# 3V3BUCK.net
KiCad netlist of a schematic drawn in Altium Designer
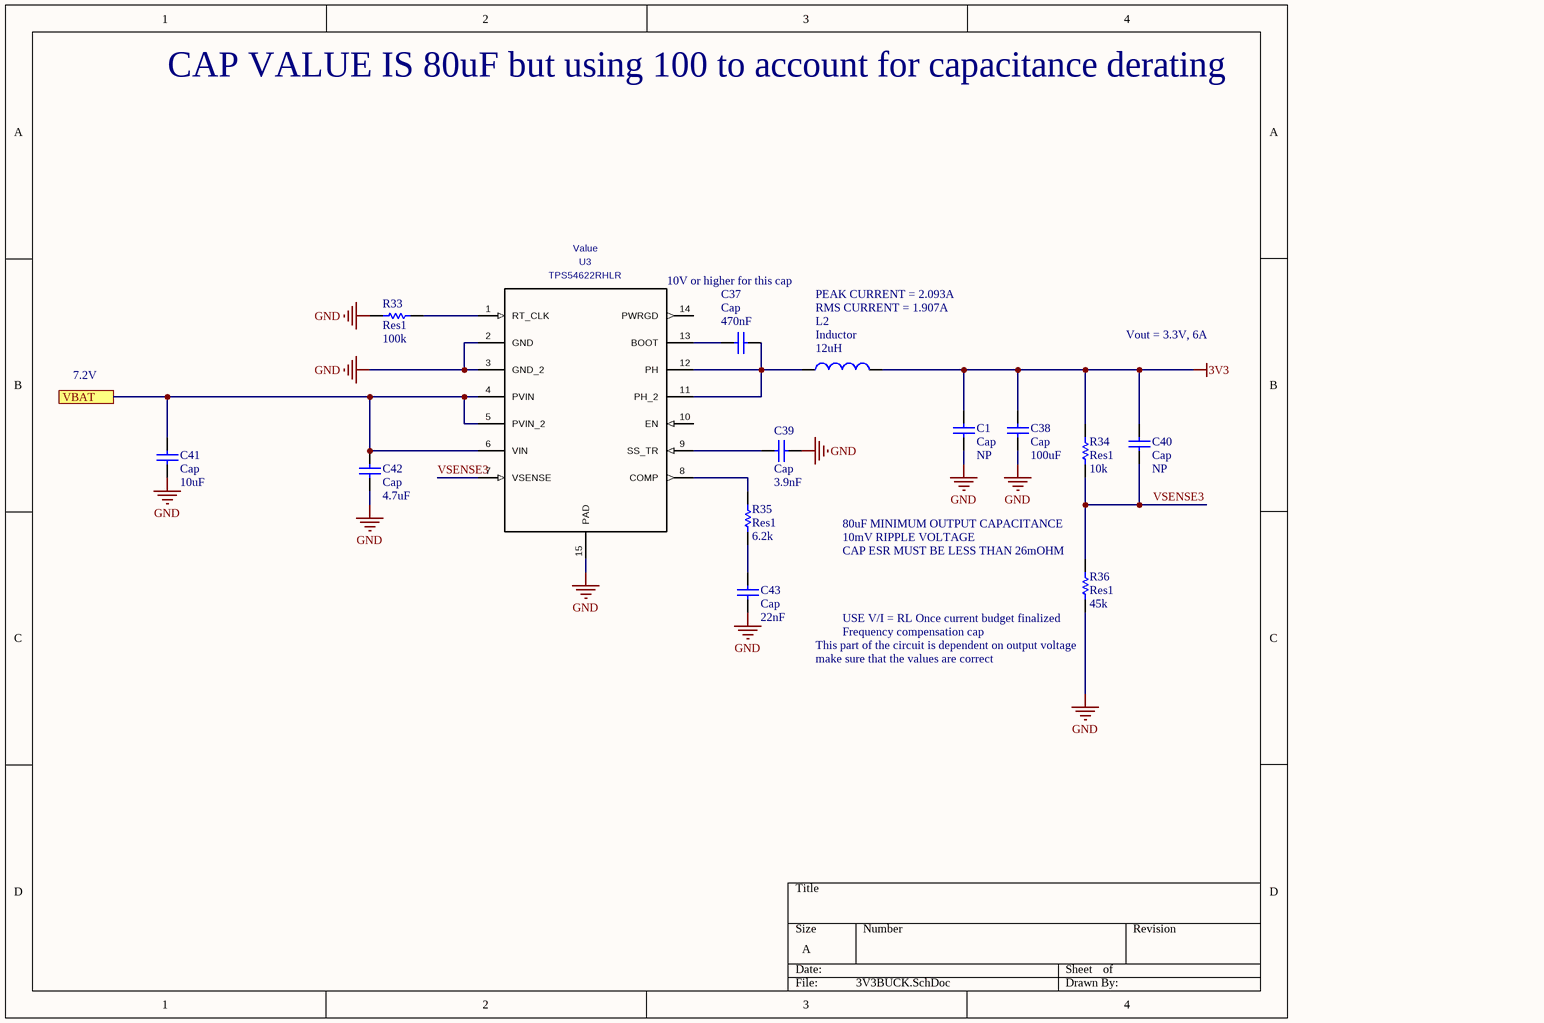
[diagram p0: 3V3BUCK.SchDoc]

(export (version "E")
  (design (tool "Eeschema 10.0.6"))
  (components
    (comp (ref "C1")
      (value "Cap")
      (footprint "1608[0603]")
      (description "Capacitor")
      (fields (field (name "ALTIUM_VALUE") "NP") (field (name "PUBLISHER") "Altium Limited"))
      (libsource (lib "Miscellaneous Devices") (part "Cap"))
    )
    (comp (ref "C37")
      (value "Cap")
      (footprint "0402-A")
      (description "Capacitor")
      (fields (field (name "ALTIUM_VALUE") "470nF") (field (name "PUBLISHER") "Altium Limited"))
      (libsource (lib "Miscellaneous Devices") (part "Cap"))
    )
    (comp (ref "C38")
      (value "Cap")
      (footprint "C1210")
      (description "Capacitor")
      (fields (field (name "ALTIUM_VALUE") "100uF") (field (name "PUBLISHER") "Altium Limited"))
      (libsource (lib "Miscellaneous Devices") (part "Cap"))
    )
    (comp (ref "C39")
      (value "Cap")
      (footprint "0402-A")
      (description "Capacitor")
      (fields (field (name "ALTIUM_VALUE") "3.9nF") (field (name "PUBLISHER") "Altium Limited"))
      (libsource (lib "Miscellaneous Devices") (part "Cap"))
    )
    (comp (ref "C40")
      (value "Cap")
      (footprint "1608[0603]")
      (description "Capacitor")
      (fields (field (name "ALTIUM_VALUE") "NP") (field (name "PUBLISHER") "Altium Limited"))
      (libsource (lib "Miscellaneous Devices") (part "Cap"))
    )
    (comp (ref "C41")
      (value "Cap")
      (footprint "6-0805_M")
      (description "Capacitor")
      (fields (field (name "ALTIUM_VALUE") "10uF") (field (name "PUBLISHER") "Altium Limited"))
      (libsource (lib "Miscellaneous Devices") (part "Cap"))
    )
    (comp (ref "C42")
      (value "Cap")
      (footprint "6-0805_M")
      (description "Capacitor")
      (fields (field (name "ALTIUM_VALUE") "4.7uF") (field (name "PUBLISHER") "Altium Limited"))
      (libsource (lib "Miscellaneous Devices") (part "Cap"))
    )
    (comp (ref "C43")
      (value "Cap")
      (footprint "0402-A")
      (description "Capacitor")
      (fields (field (name "ALTIUM_VALUE") "22nF") (field (name "PUBLISHER") "Altium Limited"))
      (libsource (lib "Miscellaneous Devices") (part "Cap"))
    )
    (comp (ref "L2")
      (value "Inductor")
      (footprint "IND_BOURNS_SRR1260")
      (fields (field (name "ALTIUM_VALUE") "12uH") (field (name "PUBLISHER") "Altium Limited"))
      (libsource (lib "Miscellaneous Devices") (part "Inductor"))
    )
    (comp (ref "R33")
      (value "Res1")
      (footprint "0402-A")
      (description "Resistor")
      (fields (field (name "ALTIUM_VALUE") "100k") (field (name "PUBLISHER") "Altium Limited"))
      (libsource (lib "Miscellaneous Devices") (part "Res1"))
    )
    (comp (ref "R34")
      (value "Res1")
      (footprint "0402-A")
      (description "Resistor")
      (fields (field (name "ALTIUM_VALUE") "10k") (field (name "PUBLISHER") "Altium Limited"))
      (libsource (lib "Miscellaneous Devices") (part "Res1"))
    )
    (comp (ref "R35")
      (value "Res1")
      (footprint "0402-A")
      (description "Resistor")
      (fields (field (name "ALTIUM_VALUE") "6.2k") (field (name "PUBLISHER") "Altium Limited"))
      (libsource (lib "Miscellaneous Devices") (part "Res1"))
    )
    (comp (ref "R36")
      (value "Res1")
      (footprint "0402-A")
      (description "Resistor 1%")
      (fields (field (name "ALTIUM_VALUE") "45k") (field (name "PUBLISHER") "Altium Limited"))
      (libsource (lib "Miscellaneous Devices") (part "Res1"))
    )
    (comp (ref "U3")
      (value "TPS54622RHLR")
      (footprint "RHL0014A")
      (fields (field (name "MANUFACTURER") "Texas Instruments") (field (name "ALTIUM_VALUE") "Value"))
      (libsource (lib "AltiumV15") (part "TPS54622RHLR"))
    )
  )
  (nets
    (net (code "1") (name "/VBAT") (class "Default")
      (node (ref "C41") (pin "2") (pinfunction "2_2") (pintype "passive"))
      (node (ref "C42") (pin "2") (pinfunction "2_2") (pintype "passive"))
      (node (ref "U3") (pin "4") (pinfunction "PVIN_4") (pintype "power_in"))
      (node (ref "U3") (pin "5") (pinfunction "PVIN_2_5") (pintype "power_in"))
      (node (ref "U3") (pin "6") (pinfunction "VIN_6") (pintype "power_in"))
    )
    (net (code "2") (name "/VSENSE3") (class "Default")
      (node (ref "C40") (pin "1") (pinfunction "1_1") (pintype "passive"))
      (node (ref "R34") (pin "2") (pinfunction "2_2") (pintype "passive"))
      (node (ref "R36") (pin "2") (pinfunction "2_2") (pintype "passive"))
      (node (ref "U3") (pin "7") (pinfunction "VSENSE_7") (pintype "input"))
    )
    (net (code "3") (name "3V3") (class "Default")
      (node (ref "C1") (pin "2") (pinfunction "2_2") (pintype "passive"))
      (node (ref "C38") (pin "2") (pinfunction "2_2") (pintype "passive"))
      (node (ref "C40") (pin "2") (pinfunction "2_2") (pintype "passive"))
      (node (ref "L2") (pin "2") (pinfunction "2_2") (pintype "passive"))
      (node (ref "R34") (pin "1") (pinfunction "1_1") (pintype "passive"))
    )
    (net (code "4") (name "GND") (class "Default")
      (node (ref "C1") (pin "1") (pinfunction "1_1") (pintype "passive"))
      (node (ref "C38") (pin "1") (pinfunction "1_1") (pintype "passive"))
      (node (ref "C39") (pin "1") (pinfunction "1_1") (pintype "passive"))
      (node (ref "C41") (pin "1") (pinfunction "1_1") (pintype "passive"))
      (node (ref "C42") (pin "1") (pinfunction "1_1") (pintype "passive"))
      (node (ref "C43") (pin "1") (pinfunction "1_1") (pintype "passive"))
      (node (ref "R33") (pin "1") (pinfunction "1_1") (pintype "passive"))
      (node (ref "R36") (pin "1") (pinfunction "1_1") (pintype "passive"))
      (node (ref "U3") (pin "15") (pinfunction "PAD_15") (pintype "power_in"))
      (node (ref "U3") (pin "2") (pinfunction "GND_2") (pintype "power_in"))
      (node (ref "U3") (pin "3") (pinfunction "GND_2_3") (pintype "power_in"))
    )
    (net (code "5") (name "Net-(C43-Pad2)") (class "Default")
      (node (ref "C43") (pin "2") (pinfunction "2_2") (pintype "passive"))
      (node (ref "R35") (pin "1") (pinfunction "1_1") (pintype "passive"))
    )
    (net (code "6") (name "Net-(U3-BOOT)") (class "Default")
      (node (ref "C37") (pin "1") (pinfunction "1_1") (pintype "passive"))
      (node (ref "U3") (pin "13") (pinfunction "BOOT_13") (pintype "power_in"))
    )
    (net (code "7") (name "Net-(U3-COMP)") (class "Default")
      (node (ref "R35") (pin "2") (pinfunction "2_2") (pintype "passive"))
      (node (ref "U3") (pin "8") (pinfunction "COMP_8") (pintype "output"))
    )
    (net (code "8") (name "Net-(U3-PH)") (class "Default")
      (node (ref "C37") (pin "2") (pinfunction "2_2") (pintype "passive"))
      (node (ref "L2") (pin "1") (pinfunction "1_1") (pintype "passive"))
      (node (ref "U3") (pin "11") (pinfunction "PH_2_11") (pintype "power_in"))
      (node (ref "U3") (pin "12") (pinfunction "PH_12") (pintype "power_in"))
    )
    (net (code "9") (name "Net-(U3-RT_CLK)") (class "Default")
      (node (ref "R33") (pin "2") (pinfunction "2_2") (pintype "passive"))
      (node (ref "U3") (pin "1") (pinfunction "RT_CLK_1") (pintype "input"))
    )
    (net (code "10") (name "Net-(U3-SS_TR)") (class "Default")
      (node (ref "C39") (pin "2") (pinfunction "2_2") (pintype "passive"))
      (node (ref "U3") (pin "9") (pinfunction "SS_TR_9") (pintype "input"))
    )
    (net (code "11") (name "unconnected-(U3-EN-Pad10)") (class "Default")
      (node (ref "U3") (pin "10") (pinfunction "EN_10") (pintype "input"))
    )
    (net (code "12") (name "unconnected-(U3-PWRGD-Pad14)") (class "Default")
      (node (ref "U3") (pin "14") (pinfunction "PWRGD_14") (pintype "output"))
    )
  )
)
